# Xbee_Communications_Board.net
KiCad netlist of a schematic drawn in EAGLE
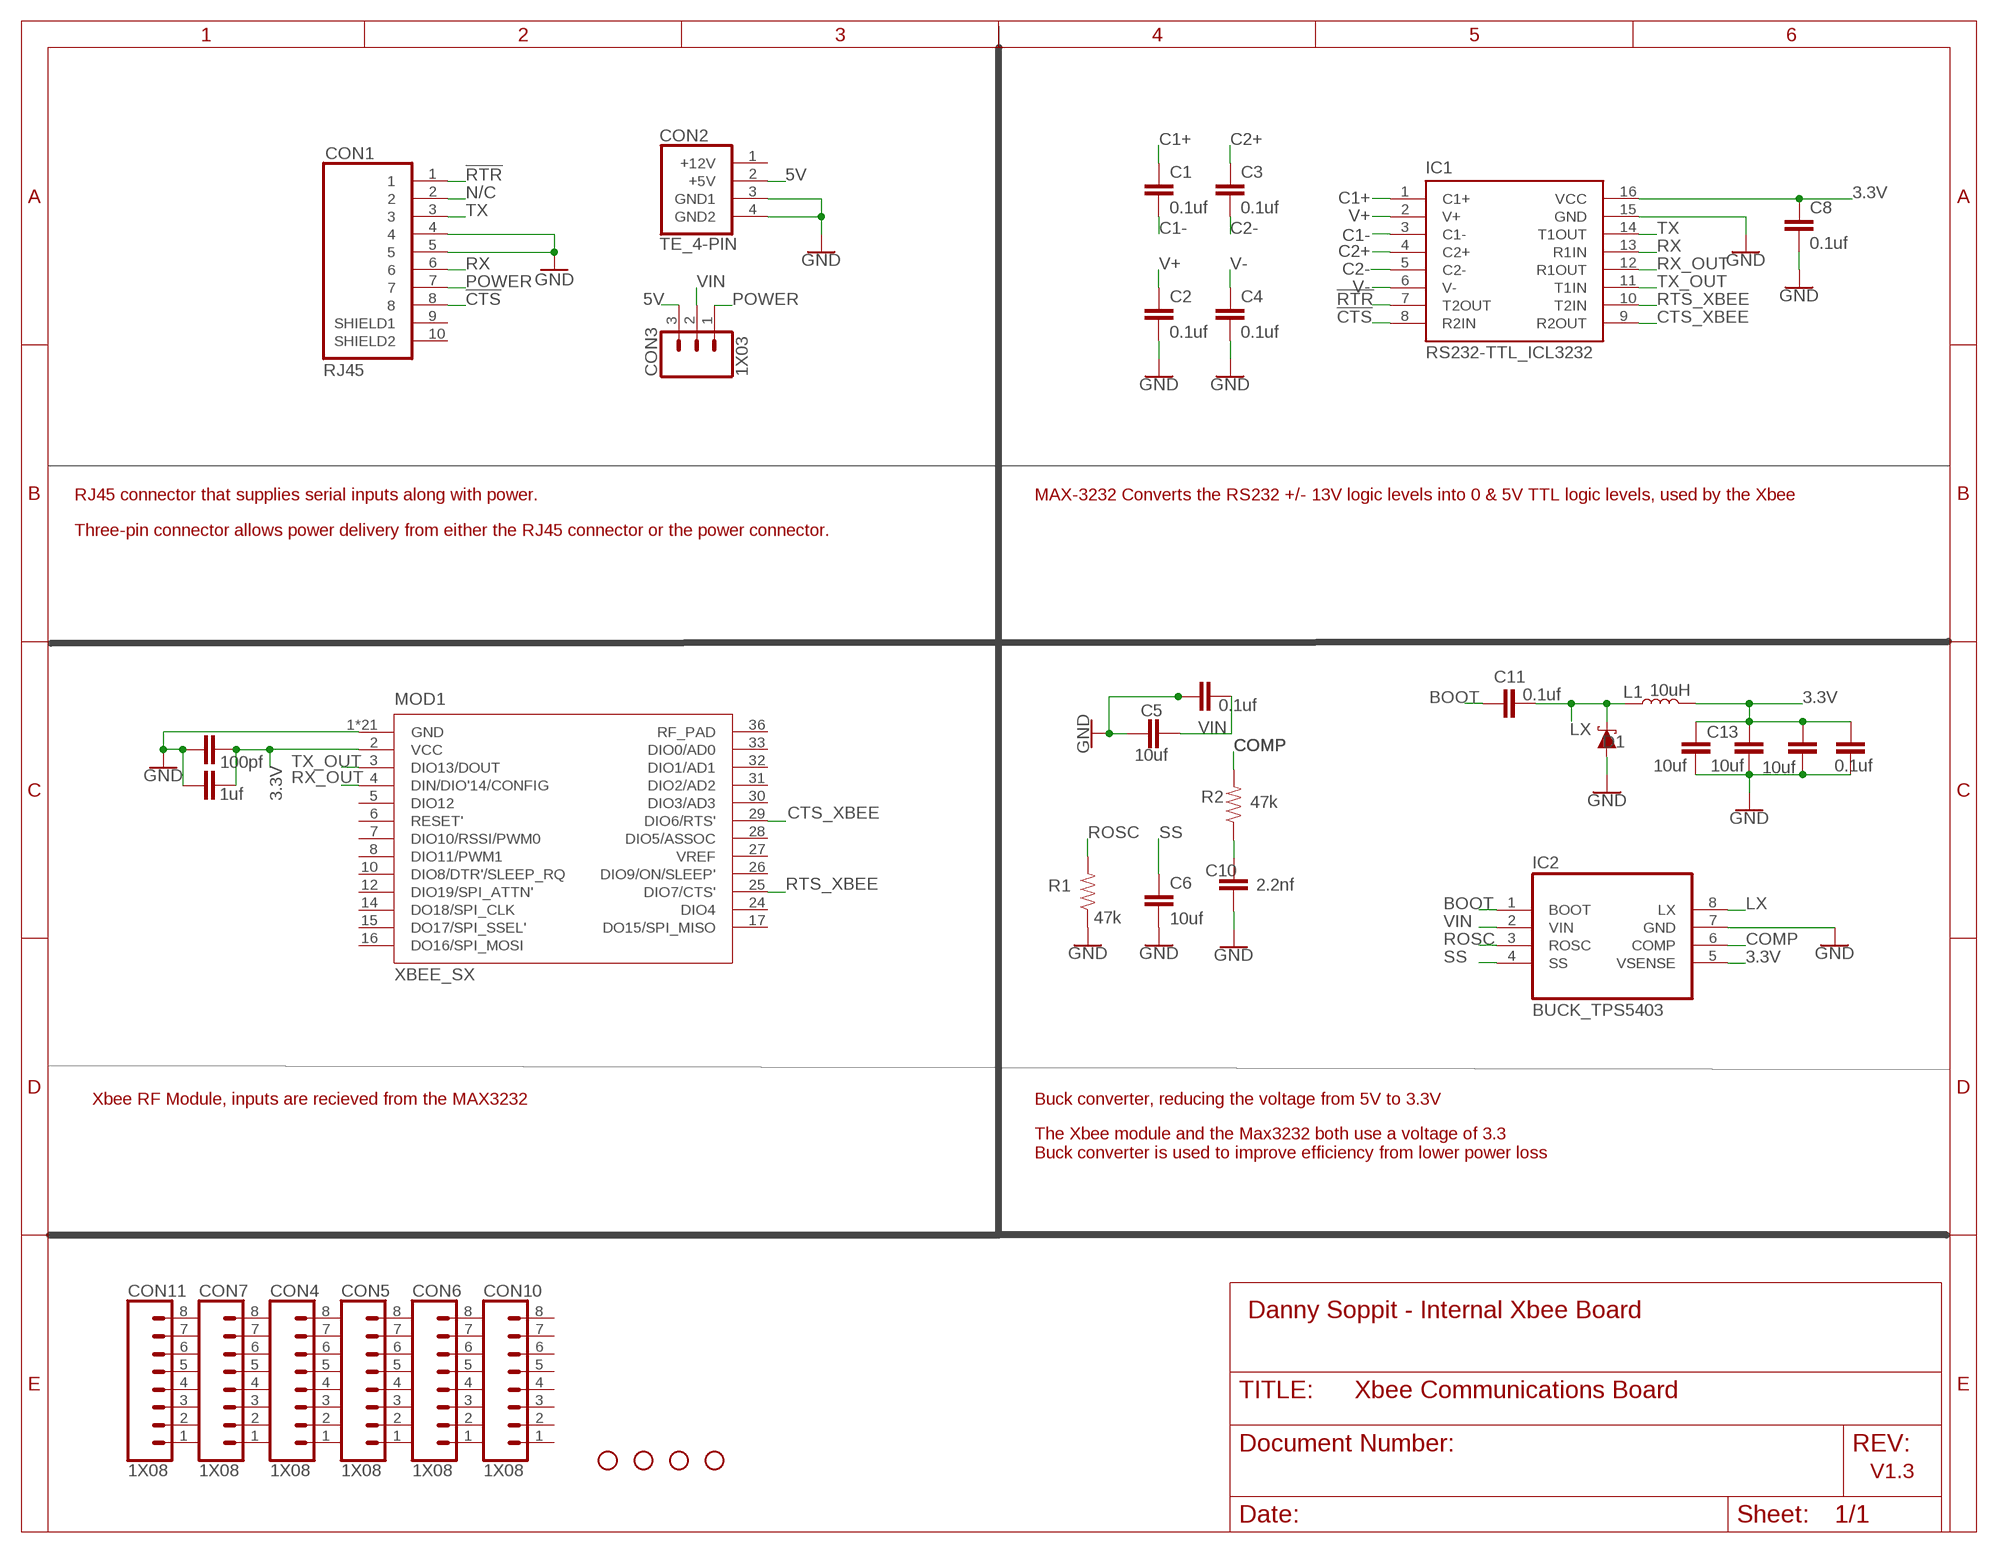
[diagram p0: schematic, sheet 1]

(export (version "E")
  (design (tool "Eeschema 10.0.6"))
  (components
    (comp (ref "C1")
      (value "0.1uf")
      (footprint "eagle-import:0805")
      (libsource (lib "eagle-import") (part "CAPACITOR_0805"))
    )
    (comp (ref "C2")
      (value "0.1uf")
      (footprint "eagle-import:0805")
      (libsource (lib "eagle-import") (part "CAPACITOR_0805"))
    )
    (comp (ref "C3")
      (value "0.1uf")
      (footprint "eagle-import:0805")
      (libsource (lib "eagle-import") (part "CAPACITOR_0805"))
    )
    (comp (ref "C4")
      (value "0.1uf")
      (footprint "eagle-import:0805")
      (libsource (lib "eagle-import") (part "CAPACITOR_0805"))
    )
    (comp (ref "C5")
      (value "10uf")
      (footprint "eagle-import:0805")
      (libsource (lib "eagle-import") (part "CAPACITOR_0805"))
    )
    (comp (ref "C6")
      (value "10uf")
      (footprint "eagle-import:0805")
      (libsource (lib "eagle-import") (part "CAPACITOR_0805"))
    )
    (comp (ref "C7")
      (value "0.1uf")
      (footprint "eagle-import:0805")
      (libsource (lib "eagle-import") (part "CAPACITOR_0805"))
    )
    (comp (ref "C8")
      (value "0.1uf")
      (footprint "eagle-import:0805")
      (libsource (lib "eagle-import") (part "CAPACITOR_0805"))
    )
    (comp (ref "C9")
      (value "100pf")
      (footprint "eagle-import:0805")
      (libsource (lib "eagle-import") (part "CAPACITOR_0805"))
    )
    (comp (ref "C10")
      (value "2.2nf")
      (footprint "eagle-import:0805")
      (libsource (lib "eagle-import") (part "CAPACITOR_0805"))
    )
    (comp (ref "C11")
      (value "0.1uf")
      (footprint "eagle-import:0805")
      (libsource (lib "eagle-import") (part "CAPACITOR_0805"))
    )
    (comp (ref "C12")
      (value "10uf")
      (footprint "eagle-import:0805")
      (libsource (lib "eagle-import") (part "CAPACITOR_0805"))
    )
    (comp (ref "C13")
      (value "10uf")
      (footprint "eagle-import:0805")
      (libsource (lib "eagle-import") (part "CAPACITOR_0805"))
    )
    (comp (ref "C14")
      (value "10uf")
      (footprint "eagle-import:0805")
      (libsource (lib "eagle-import") (part "CAPACITOR_0805"))
    )
    (comp (ref "C15")
      (value "0.1uf")
      (footprint "eagle-import:0805")
      (libsource (lib "eagle-import") (part "CAPACITOR_0805"))
    )
    (comp (ref "C16")
      (value "1uf")
      (footprint "eagle-import:0805")
      (libsource (lib "eagle-import") (part "CAPACITOR_0805"))
    )
    (comp (ref "CON1")
      (value "RJ45")
      (footprint "eagle-import:RJ45")
      (libsource (lib "eagle-import") (part "RJ45"))
    )
    (comp (ref "CON2")
      (value "TE_4-PIN")
      (footprint "eagle-import:TE_4-PIN")
      (libsource (lib "eagle-import") (part "TE_4-PIN"))
    )
    (comp (ref "CON3")
      (value "1X03")
      (footprint "eagle-import:1X03")
      (libsource (lib "eagle-import") (part "1X03"))
    )
    (comp (ref "CON4")
      (value "1X08")
      (footprint "eagle-import:1X08")
      (libsource (lib "eagle-import") (part "1X08"))
    )
    (comp (ref "CON5")
      (value "1X08")
      (footprint "eagle-import:1X08")
      (libsource (lib "eagle-import") (part "1X08"))
    )
    (comp (ref "CON6")
      (value "1X08")
      (footprint "eagle-import:1X08")
      (libsource (lib "eagle-import") (part "1X08"))
    )
    (comp (ref "CON7")
      (value "1X08")
      (footprint "eagle-import:1X08")
      (libsource (lib "eagle-import") (part "1X08"))
    )
    (comp (ref "CON10")
      (value "1X08")
      (footprint "eagle-import:1X08")
      (libsource (lib "eagle-import") (part "1X08"))
    )
    (comp (ref "CON11")
      (value "1X08")
      (footprint "eagle-import:1X08")
      (libsource (lib "eagle-import") (part "1X08"))
    )
    (comp (ref "D1")
      (value "DIODE_SCHOTTKY_DO-214AA")
      (footprint "eagle-import:DO214AA")
      (libsource (lib "eagle-import") (part "DIODE_SCHOTTKY_DO-214AA"))
    )
    (comp (ref "H1")
      (value "STAND-OFF")
      (footprint "eagle-import:STAND-OFF")
      (libsource (lib "eagle-import") (part "STAND-OFF"))
    )
    (comp (ref "H2")
      (value "STAND-OFF")
      (footprint "eagle-import:STAND-OFF")
      (libsource (lib "eagle-import") (part "STAND-OFF"))
    )
    (comp (ref "H3")
      (value "STAND-OFF")
      (footprint "eagle-import:STAND-OFF")
      (libsource (lib "eagle-import") (part "STAND-OFF"))
    )
    (comp (ref "H4")
      (value "STAND-OFF")
      (footprint "eagle-import:STAND-OFF")
      (libsource (lib "eagle-import") (part "STAND-OFF"))
    )
    (comp (ref "IC1")
      (value "RS232-TTL_ICL3232")
      (footprint "eagle-import:DIP16")
      (libsource (lib "eagle-import") (part "RS232-TTL_ICL3232"))
    )
    (comp (ref "IC2")
      (value "BUCK_TPS5403")
      (footprint "eagle-import:SOIC8")
      (libsource (lib "eagle-import") (part "BUCK_TPS5403"))
    )
    (comp (ref "L1")
      (value "10uH")
      (footprint "eagle-import:INDUCTOR_MURATA_DEM8030C")
      (libsource (lib "eagle-import") (part "INDUCTOR_MURATA_DEM8030C"))
    )
    (comp (ref "MOD1")
      (value "XBEE_SX")
      (footprint "eagle-import:XBEE_SX")
      (libsource (lib "eagle-import") (part "XBEE_SX"))
    )
    (comp (ref "R1")
      (value "47k")
      (footprint "eagle-import:0805")
      (libsource (lib "eagle-import") (part "RESISTOR_0805"))
    )
    (comp (ref "R2")
      (value "47k")
      (footprint "eagle-import:0805")
      (libsource (lib "eagle-import") (part "RESISTOR_0805"))
    )
  )
  (nets
    (net (code "1") (name "/3.3V") (class "Default")
      (node (ref "C12") (pin "1") (pinfunction "1_1") (pintype "passive"))
      (node (ref "C13") (pin "2") (pinfunction "2_2") (pintype "passive"))
      (node (ref "C14") (pin "2") (pinfunction "2_2") (pintype "passive"))
      (node (ref "C15") (pin "2") (pinfunction "2_2") (pintype "passive"))
      (node (ref "C16") (pin "2") (pinfunction "2_2") (pintype "passive"))
      (node (ref "C8") (pin "1") (pinfunction "1_1") (pintype "passive"))
      (node (ref "C9") (pin "2") (pinfunction "2_2") (pintype "passive"))
      (node (ref "IC1") (pin "16") (pinfunction "VCC_16") (pintype "bidirectional"))
      (node (ref "IC2") (pin "5") (pinfunction "VSENSE_5") (pintype "bidirectional"))
      (node (ref "L1") (pin "P$2") (pinfunction "2_P$2") (pintype "passive"))
      (node (ref "MOD1") (pin "2") (pinfunction "VCC_2") (pintype "bidirectional"))
    )
    (net (code "2") (name "/5V") (class "Default")
      (node (ref "CON2") (pin "2") (pinfunction "+5V_2") (pintype "passive"))
      (node (ref "CON3") (pin "3") (pinfunction "3_3") (pintype "passive"))
    )
    (net (code "3") (name "/BOOT") (class "Default")
      (node (ref "C11") (pin "1") (pinfunction "1_1") (pintype "passive"))
      (node (ref "IC2") (pin "1") (pinfunction "BOOT_1") (pintype "bidirectional"))
    )
    (net (code "4") (name "/C1+") (class "Default")
      (node (ref "C1") (pin "1") (pinfunction "1_1") (pintype "passive"))
      (node (ref "IC1") (pin "1") (pinfunction "C1+_1") (pintype "bidirectional"))
    )
    (net (code "5") (name "/C1-") (class "Default")
      (node (ref "C1") (pin "2") (pinfunction "2_2") (pintype "passive"))
      (node (ref "IC1") (pin "3") (pinfunction "C1-_3") (pintype "bidirectional"))
    )
    (net (code "6") (name "/C2+") (class "Default")
      (node (ref "C3") (pin "1") (pinfunction "1_1") (pintype "passive"))
      (node (ref "IC1") (pin "4") (pinfunction "C2+_4") (pintype "bidirectional"))
    )
    (net (code "7") (name "/C2-") (class "Default")
      (node (ref "C3") (pin "2") (pinfunction "2_2") (pintype "passive"))
      (node (ref "IC1") (pin "5") (pinfunction "C2-_5") (pintype "bidirectional"))
    )
    (net (code "8") (name "/COMP") (class "Default")
      (node (ref "IC2") (pin "6") (pinfunction "COMP_6") (pintype "bidirectional"))
      (node (ref "R2") (pin "2") (pinfunction "2_2") (pintype "passive"))
    )
    (net (code "9") (name "/CTS_XBEE") (class "Default")
      (node (ref "IC1") (pin "9") (pinfunction "R2OUT_9") (pintype "bidirectional"))
      (node (ref "MOD1") (pin "29") (pinfunction "DIO6/RTS'_29") (pintype "bidirectional"))
    )
    (net (code "10") (name "/LX") (class "Default")
      (node (ref "C11") (pin "2") (pinfunction "2_2") (pintype "passive"))
      (node (ref "D1") (pin "C") (pinfunction "C_C") (pintype "passive"))
      (node (ref "IC2") (pin "8") (pinfunction "LX_8") (pintype "bidirectional"))
      (node (ref "L1") (pin "P$1") (pinfunction "1_P$1") (pintype "passive"))
    )
    (net (code "11") (name "/N{slash}C") (class "Default")
      (node (ref "CON1") (pin "2") (pinfunction "2_2") (pintype "passive"))
    )
    (net (code "12") (name "/POWER") (class "Default")
      (node (ref "CON1") (pin "7") (pinfunction "7_7") (pintype "passive"))
      (node (ref "CON3") (pin "1") (pinfunction "1_1") (pintype "passive"))
    )
    (net (code "13") (name "/ROSC") (class "Default")
      (node (ref "IC2") (pin "3") (pinfunction "ROSC_3") (pintype "bidirectional"))
      (node (ref "R1") (pin "2") (pinfunction "2_2") (pintype "passive"))
    )
    (net (code "14") (name "/RTS_XBEE") (class "Default")
      (node (ref "IC1") (pin "10") (pinfunction "T2IN_10") (pintype "bidirectional"))
      (node (ref "MOD1") (pin "25") (pinfunction "DIO7/CTS'_25") (pintype "bidirectional"))
    )
    (net (code "15") (name "/RX") (class "Default")
      (node (ref "CON1") (pin "6") (pinfunction "6_6") (pintype "passive"))
      (node (ref "IC1") (pin "13") (pinfunction "R1IN_13") (pintype "bidirectional"))
    )
    (net (code "16") (name "/RX_OUT") (class "Default")
      (node (ref "IC1") (pin "12") (pinfunction "R1OUT_12") (pintype "bidirectional"))
      (node (ref "MOD1") (pin "4") (pinfunction "DIN/DIO'14/CONFIG_4") (pintype "bidirectional"))
    )
    (net (code "17") (name "/SS") (class "Default")
      (node (ref "C6") (pin "1") (pinfunction "1_1") (pintype "passive"))
      (node (ref "IC2") (pin "4") (pinfunction "SS_4") (pintype "bidirectional"))
    )
    (net (code "18") (name "/TX") (class "Default")
      (node (ref "CON1") (pin "3") (pinfunction "3_3") (pintype "passive"))
      (node (ref "IC1") (pin "14") (pinfunction "T1OUT_14") (pintype "bidirectional"))
    )
    (net (code "19") (name "/TX_OUT") (class "Default")
      (node (ref "IC1") (pin "11") (pinfunction "T1IN_11") (pintype "bidirectional"))
      (node (ref "MOD1") (pin "3") (pinfunction "DIO13/DOUT_3") (pintype "bidirectional"))
    )
    (net (code "20") (name "/V+") (class "Default")
      (node (ref "C2") (pin "1") (pinfunction "1_1") (pintype "passive"))
      (node (ref "IC1") (pin "2") (pinfunction "V+_2") (pintype "bidirectional"))
    )
    (net (code "21") (name "/V-") (class "Default")
      (node (ref "C4") (pin "1") (pinfunction "1_1") (pintype "passive"))
      (node (ref "IC1") (pin "6") (pinfunction "V-_6") (pintype "bidirectional"))
    )
    (net (code "22") (name "/VIN") (class "Default")
      (node (ref "C5") (pin "2") (pinfunction "2_2") (pintype "passive"))
      (node (ref "C7") (pin "2") (pinfunction "2_2") (pintype "passive"))
      (node (ref "CON3") (pin "2") (pinfunction "2_2") (pintype "passive"))
      (node (ref "IC2") (pin "2") (pinfunction "VIN_2") (pintype "bidirectional"))
    )
    (net (code "23") (name "/~{CTS}") (class "Default")
      (node (ref "CON1") (pin "8") (pinfunction "8_8") (pintype "passive"))
      (node (ref "IC1") (pin "8") (pinfunction "R2IN_8") (pintype "bidirectional"))
    )
    (net (code "24") (name "/~{RTR}") (class "Default")
      (node (ref "CON1") (pin "1") (pinfunction "1_1") (pintype "passive"))
      (node (ref "IC1") (pin "7") (pinfunction "T2OUT_7") (pintype "bidirectional"))
    )
    (net (code "25") (name "GND") (class "Default")
      (node (ref "C10") (pin "1") (pinfunction "1_1") (pintype "passive"))
      (node (ref "C12") (pin "2") (pinfunction "2_2") (pintype "passive"))
      (node (ref "C13") (pin "1") (pinfunction "1_1") (pintype "passive"))
      (node (ref "C14") (pin "1") (pinfunction "1_1") (pintype "passive"))
      (node (ref "C15") (pin "1") (pinfunction "1_1") (pintype "passive"))
      (node (ref "C16") (pin "1") (pinfunction "1_1") (pintype "passive"))
      (node (ref "C2") (pin "2") (pinfunction "2_2") (pintype "passive"))
      (node (ref "C4") (pin "2") (pinfunction "2_2") (pintype "passive"))
      (node (ref "C5") (pin "1") (pinfunction "1_1") (pintype "passive"))
      (node (ref "C6") (pin "2") (pinfunction "2_2") (pintype "passive"))
      (node (ref "C7") (pin "1") (pinfunction "1_1") (pintype "passive"))
      (node (ref "C8") (pin "2") (pinfunction "2_2") (pintype "passive"))
      (node (ref "C9") (pin "1") (pinfunction "1_1") (pintype "passive"))
      (node (ref "CON1") (pin "4") (pinfunction "4_4") (pintype "passive"))
      (node (ref "CON1") (pin "5") (pinfunction "5_5") (pintype "passive"))
      (node (ref "CON2") (pin "3") (pinfunction "GND1_3") (pintype "passive"))
      (node (ref "CON2") (pin "4") (pinfunction "GND2_4") (pintype "passive"))
      (node (ref "D1") (pin "A") (pinfunction "A_A") (pintype "passive"))
      (node (ref "IC1") (pin "15") (pinfunction "GND_15") (pintype "bidirectional"))
      (node (ref "IC2") (pin "7") (pinfunction "GND_7") (pintype "bidirectional"))
      (node (ref "MOD1") (pin "1") (pinfunction "GND_1") (pintype "bidirectional"))
      (node (ref "MOD1") (pin "11") (pinfunction "GND_11") (pintype "bidirectional"))
      (node (ref "MOD1") (pin "13") (pinfunction "GND_13") (pintype "bidirectional"))
      (node (ref "MOD1") (pin "22") (pinfunction "GND_22") (pintype "bidirectional"))
      (node (ref "MOD1") (pin "35") (pinfunction "GND_35") (pintype "bidirectional"))
      (node (ref "MOD1") (pin "38_1") (pinfunction "GND_38_1") (pintype "bidirectional"))
      (node (ref "MOD1") (pin "38_10") (pinfunction "GND_38_10") (pintype "bidirectional"))
      (node (ref "MOD1") (pin "38_11") (pinfunction "GND_38_11") (pintype "bidirectional"))
      (node (ref "MOD1") (pin "38_12") (pinfunction "GND_38_12") (pintype "bidirectional"))
      (node (ref "MOD1") (pin "38_13") (pinfunction "GND_38_13") (pintype "bidirectional"))
      (node (ref "MOD1") (pin "38_14") (pinfunction "GND_38_14") (pintype "bidirectional"))
      (node (ref "MOD1") (pin "38_15") (pinfunction "GND_38_15") (pintype "bidirectional"))
      (node (ref "MOD1") (pin "38_16") (pinfunction "GND_38_16") (pintype "bidirectional"))
      (node (ref "MOD1") (pin "38_2") (pinfunction "GND_38_2") (pintype "bidirectional"))
      (node (ref "MOD1") (pin "38_3") (pinfunction "GND_38_3") (pintype "bidirectional"))
      (node (ref "MOD1") (pin "38_4") (pinfunction "GND_38_4") (pintype "bidirectional"))
      (node (ref "MOD1") (pin "38_5") (pinfunction "GND_38_5") (pintype "bidirectional"))
      (node (ref "MOD1") (pin "38_6") (pinfunction "GND_38_6") (pintype "bidirectional"))
      (node (ref "MOD1") (pin "38_7") (pinfunction "GND_38_7") (pintype "bidirectional"))
      (node (ref "MOD1") (pin "38_8") (pinfunction "GND_38_8") (pintype "bidirectional"))
      (node (ref "MOD1") (pin "38_9") (pinfunction "GND_38_9") (pintype "bidirectional"))
      (node (ref "R1") (pin "1") (pinfunction "1_1") (pintype "passive"))
    )
    (net (code "26") (name "Net-(C10-Pad2)") (class "Default")
      (node (ref "C10") (pin "2") (pinfunction "2_2") (pintype "passive"))
      (node (ref "R2") (pin "1") (pinfunction "1_1") (pintype "passive"))
    )
    (net (code "27") (name "unconnected-(CON1-SHIELD1-Pad9)") (class "Default")
      (node (ref "CON1") (pin "9") (pinfunction "SHIELD1_9") (pintype "passive"))
    )
    (net (code "28") (name "unconnected-(CON1-SHIELD2-Pad10)") (class "Default")
      (node (ref "CON1") (pin "10") (pinfunction "SHIELD2_10") (pintype "passive"))
    )
    (net (code "29") (name "unconnected-(CON2-+12V-Pad1)") (class "Default")
      (node (ref "CON2") (pin "1") (pinfunction "+12V_1") (pintype "passive"))
    )
    (net (code "30") (name "unconnected-(CON4-Pad1)") (class "Default")
      (node (ref "CON4") (pin "1") (pinfunction "1_1") (pintype "passive"))
    )
    (net (code "31") (name "unconnected-(CON4-Pad2)") (class "Default")
      (node (ref "CON4") (pin "2") (pinfunction "2_2") (pintype "passive"))
    )
    (net (code "32") (name "unconnected-(CON4-Pad3)") (class "Default")
      (node (ref "CON4") (pin "3") (pinfunction "3_3") (pintype "passive"))
    )
    (net (code "33") (name "unconnected-(CON4-Pad4)") (class "Default")
      (node (ref "CON4") (pin "4") (pinfunction "4_4") (pintype "passive"))
    )
    (net (code "34") (name "unconnected-(CON4-Pad5)") (class "Default")
      (node (ref "CON4") (pin "5") (pinfunction "5_5") (pintype "passive"))
    )
    (net (code "35") (name "unconnected-(CON4-Pad6)") (class "Default")
      (node (ref "CON4") (pin "6") (pinfunction "6_6") (pintype "passive"))
    )
    (net (code "36") (name "unconnected-(CON4-Pad7)") (class "Default")
      (node (ref "CON4") (pin "7") (pinfunction "7_7") (pintype "passive"))
    )
    (net (code "37") (name "unconnected-(CON4-Pad8)") (class "Default")
      (node (ref "CON4") (pin "8") (pinfunction "8_8") (pintype "passive"))
    )
    (net (code "38") (name "unconnected-(CON5-Pad1)") (class "Default")
      (node (ref "CON5") (pin "1") (pinfunction "1_1") (pintype "passive"))
    )
    (net (code "39") (name "unconnected-(CON5-Pad2)") (class "Default")
      (node (ref "CON5") (pin "2") (pinfunction "2_2") (pintype "passive"))
    )
    (net (code "40") (name "unconnected-(CON5-Pad3)") (class "Default")
      (node (ref "CON5") (pin "3") (pinfunction "3_3") (pintype "passive"))
    )
    (net (code "41") (name "unconnected-(CON5-Pad4)") (class "Default")
      (node (ref "CON5") (pin "4") (pinfunction "4_4") (pintype "passive"))
    )
    (net (code "42") (name "unconnected-(CON5-Pad5)") (class "Default")
      (node (ref "CON5") (pin "5") (pinfunction "5_5") (pintype "passive"))
    )
    (net (code "43") (name "unconnected-(CON5-Pad6)") (class "Default")
      (node (ref "CON5") (pin "6") (pinfunction "6_6") (pintype "passive"))
    )
    (net (code "44") (name "unconnected-(CON5-Pad7)") (class "Default")
      (node (ref "CON5") (pin "7") (pinfunction "7_7") (pintype "passive"))
    )
    (net (code "45") (name "unconnected-(CON5-Pad8)") (class "Default")
      (node (ref "CON5") (pin "8") (pinfunction "8_8") (pintype "passive"))
    )
    (net (code "46") (name "unconnected-(CON6-Pad1)") (class "Default")
      (node (ref "CON6") (pin "1") (pinfunction "1_1") (pintype "passive"))
    )
    (net (code "47") (name "unconnected-(CON6-Pad2)") (class "Default")
      (node (ref "CON6") (pin "2") (pinfunction "2_2") (pintype "passive"))
    )
    (net (code "48") (name "unconnected-(CON6-Pad3)") (class "Default")
      (node (ref "CON6") (pin "3") (pinfunction "3_3") (pintype "passive"))
    )
    (net (code "49") (name "unconnected-(CON6-Pad4)") (class "Default")
      (node (ref "CON6") (pin "4") (pinfunction "4_4") (pintype "passive"))
    )
    (net (code "50") (name "unconnected-(CON6-Pad5)") (class "Default")
      (node (ref "CON6") (pin "5") (pinfunction "5_5") (pintype "passive"))
    )
    (net (code "51") (name "unconnected-(CON6-Pad6)") (class "Default")
      (node (ref "CON6") (pin "6") (pinfunction "6_6") (pintype "passive"))
    )
    (net (code "52") (name "unconnected-(CON6-Pad7)") (class "Default")
      (node (ref "CON6") (pin "7") (pinfunction "7_7") (pintype "passive"))
    )
    (net (code "53") (name "unconnected-(CON6-Pad8)") (class "Default")
      (node (ref "CON6") (pin "8") (pinfunction "8_8") (pintype "passive"))
    )
    (net (code "54") (name "unconnected-(CON7-Pad1)") (class "Default")
      (node (ref "CON7") (pin "1") (pinfunction "1_1") (pintype "passive"))
    )
    (net (code "55") (name "unconnected-(CON7-Pad2)") (class "Default")
      (node (ref "CON7") (pin "2") (pinfunction "2_2") (pintype "passive"))
    )
    (net (code "56") (name "unconnected-(CON7-Pad3)") (class "Default")
      (node (ref "CON7") (pin "3") (pinfunction "3_3") (pintype "passive"))
    )
    (net (code "57") (name "unconnected-(CON7-Pad4)") (class "Default")
      (node (ref "CON7") (pin "4") (pinfunction "4_4") (pintype "passive"))
    )
    (net (code "58") (name "unconnected-(CON7-Pad5)") (class "Default")
      (node (ref "CON7") (pin "5") (pinfunction "5_5") (pintype "passive"))
    )
    (net (code "59") (name "unconnected-(CON7-Pad6)") (class "Default")
      (node (ref "CON7") (pin "6") (pinfunction "6_6") (pintype "passive"))
    )
    (net (code "60") (name "unconnected-(CON7-Pad7)") (class "Default")
      (node (ref "CON7") (pin "7") (pinfunction "7_7") (pintype "passive"))
    )
    (net (code "61") (name "unconnected-(CON7-Pad8)") (class "Default")
      (node (ref "CON7") (pin "8") (pinfunction "8_8") (pintype "passive"))
    )
    (net (code "62") (name "unconnected-(CON10-Pad1)") (class "Default")
      (node (ref "CON10") (pin "1") (pinfunction "1_1") (pintype "passive"))
    )
    (net (code "63") (name "unconnected-(CON10-Pad2)") (class "Default")
      (node (ref "CON10") (pin "2") (pinfunction "2_2") (pintype "passive"))
    )
    (net (code "64") (name "unconnected-(CON10-Pad3)") (class "Default")
      (node (ref "CON10") (pin "3") (pinfunction "3_3") (pintype "passive"))
    )
    (net (code "65") (name "unconnected-(CON10-Pad4)") (class "Default")
      (node (ref "CON10") (pin "4") (pinfunction "4_4") (pintype "passive"))
    )
    (net (code "66") (name "unconnected-(CON10-Pad5)") (class "Default")
      (node (ref "CON10") (pin "5") (pinfunction "5_5") (pintype "passive"))
    )
    (net (code "67") (name "unconnected-(CON10-Pad6)") (class "Default")
      (node (ref "CON10") (pin "6") (pinfunction "6_6") (pintype "passive"))
    )
    (net (code "68") (name "unconnected-(CON10-Pad7)") (class "Default")
      (node (ref "CON10") (pin "7") (pinfunction "7_7") (pintype "passive"))
    )
    (net (code "69") (name "unconnected-(CON10-Pad8)") (class "Default")
      (node (ref "CON10") (pin "8") (pinfunction "8_8") (pintype "passive"))
    )
    (net (code "70") (name "unconnected-(CON11-Pad1)") (class "Default")
      (node (ref "CON11") (pin "1") (pinfunction "1_1") (pintype "passive"))
    )
    (net (code "71") (name "unconnected-(CON11-Pad2)") (class "Default")
      (node (ref "CON11") (pin "2") (pinfunction "2_2") (pintype "passive"))
    )
    (net (code "72") (name "unconnected-(CON11-Pad3)") (class "Default")
      (node (ref "CON11") (pin "3") (pinfunction "3_3") (pintype "passive"))
    )
    (net (code "73") (name "unconnected-(CON11-Pad4)") (class "Default")
      (node (ref "CON11") (pin "4") (pinfunction "4_4") (pintype "passive"))
    )
    (net (code "74") (name "unconnected-(CON11-Pad5)") (class "Default")
      (node (ref "CON11") (pin "5") (pinfunction "5_5") (pintype "passive"))
    )
    (net (code "75") (name "unconnected-(CON11-Pad6)") (class "Default")
      (node (ref "CON11") (pin "6") (pinfunction "6_6") (pintype "passive"))
    )
    (net (code "76") (name "unconnected-(CON11-Pad7)") (class "Default")
      (node (ref "CON11") (pin "7") (pinfunction "7_7") (pintype "passive"))
    )
    (net (code "77") (name "unconnected-(CON11-Pad8)") (class "Default")
      (node (ref "CON11") (pin "8") (pinfunction "8_8") (pintype "passive"))
    )
    (net (code "78") (name "unconnected-(MOD1-DIO0{slash}AD0-Pad33)") (class "Default")
      (node (ref "MOD1") (pin "33") (pinfunction "DIO0/AD0_33") (pintype "bidirectional"))
    )
    (net (code "79") (name "unconnected-(MOD1-DIO1{slash}AD1-Pad32)") (class "Default")
      (node (ref "MOD1") (pin "32") (pinfunction "DIO1/AD1_32") (pintype "bidirectional"))
    )
    (net (code "80") (name "unconnected-(MOD1-DIO2{slash}AD2-Pad31)") (class "Default")
      (node (ref "MOD1") (pin "31") (pinfunction "DIO2/AD2_31") (pintype "bidirectional"))
    )
    (net (code "81") (name "unconnected-(MOD1-DIO3{slash}AD3-Pad30)") (class "Default")
      (node (ref "MOD1") (pin "30") (pinfunction "DIO3/AD3_30") (pintype "bidirectional"))
    )
    (net (code "82") (name "unconnected-(MOD1-DIO4-Pad24)") (class "Default")
      (node (ref "MOD1") (pin "24") (pinfunction "DIO4_24") (pintype "bidirectional"))
    )
    (net (code "83") (name "unconnected-(MOD1-DIO5{slash}ASSOC-Pad28)") (class "Default")
      (node (ref "MOD1") (pin "28") (pinfunction "DIO5/ASSOC_28") (pintype "bidirectional"))
    )
    (net (code "84") (name "unconnected-(MOD1-DIO8{slash}DTR'{slash}SLEEP_RQ-Pad10)") (class "Default")
      (node (ref "MOD1") (pin "10") (pinfunction "DIO8/DTR'/SLEEP_RQ_10") (pintype "bidirectional"))
    )
    (net (code "85") (name "unconnected-(MOD1-DIO9{slash}ON{slash}SLEEP'-Pad26)") (class "Default")
      (node (ref "MOD1") (pin "26") (pinfunction "DIO9/ON/SLEEP'_26") (pintype "bidirectional"))
    )
    (net (code "86") (name "unconnected-(MOD1-DIO10{slash}RSSI{slash}PWM0-Pad7)") (class "Default")
      (node (ref "MOD1") (pin "7") (pinfunction "DIO10/RSSI/PWM0_7") (pintype "bidirectional"))
    )
    (net (code "87") (name "unconnected-(MOD1-DIO11{slash}PWM1-Pad8)") (class "Default")
      (node (ref "MOD1") (pin "8") (pinfunction "DIO11/PWM1_8") (pintype "bidirectional"))
    )
    (net (code "88") (name "unconnected-(MOD1-DIO12-Pad5)") (class "Default")
      (node (ref "MOD1") (pin "5") (pinfunction "DIO12_5") (pintype "bidirectional"))
    )
    (net (code "89") (name "unconnected-(MOD1-DIO19{slash}SPI_ATTN'-Pad12)") (class "Default")
      (node (ref "MOD1") (pin "12") (pinfunction "DIO19/SPI_ATTN'_12") (pintype "bidirectional"))
    )
    (net (code "90") (name "unconnected-(MOD1-DO15{slash}SPI_MISO-Pad17)") (class "Default")
      (node (ref "MOD1") (pin "17") (pinfunction "DO15/SPI_MISO_17") (pintype "bidirectional"))
    )
    (net (code "91") (name "unconnected-(MOD1-DO16{slash}SPI_MOSI-Pad16)") (class "Default")
      (node (ref "MOD1") (pin "16") (pinfunction "DO16/SPI_MOSI_16") (pintype "bidirectional"))
    )
    (net (code "92") (name "unconnected-(MOD1-DO17{slash}SPI_SSEL'-Pad15)") (class "Default")
      (node (ref "MOD1") (pin "15") (pinfunction "DO17/SPI_SSEL'_15") (pintype "bidirectional"))
    )
    (net (code "93") (name "unconnected-(MOD1-DO18{slash}SPI_CLK-Pad14)") (class "Default")
      (node (ref "MOD1") (pin "14") (pinfunction "DO18/SPI_CLK_14") (pintype "bidirectional"))
    )
    (net (code "94") (name "unconnected-(MOD1-RESET'-Pad6)") (class "Default")
      (node (ref "MOD1") (pin "6") (pinfunction "RESET'_6") (pintype "bidirectional"))
    )
    (net (code "95") (name "unconnected-(MOD1-RF_PAD-Pad36)") (class "Default")
      (node (ref "MOD1") (pin "36") (pinfunction "RF_PAD_36") (pintype "bidirectional"))
    )
    (net (code "96") (name "unconnected-(MOD1-VREF-Pad27)") (class "Default")
      (node (ref "MOD1") (pin "27") (pinfunction "VREF_27") (pintype "bidirectional"))
    )
  )
)
